# iot-enviroment-shield.net
KiCad netlist of a schematic drawn in EAGLE
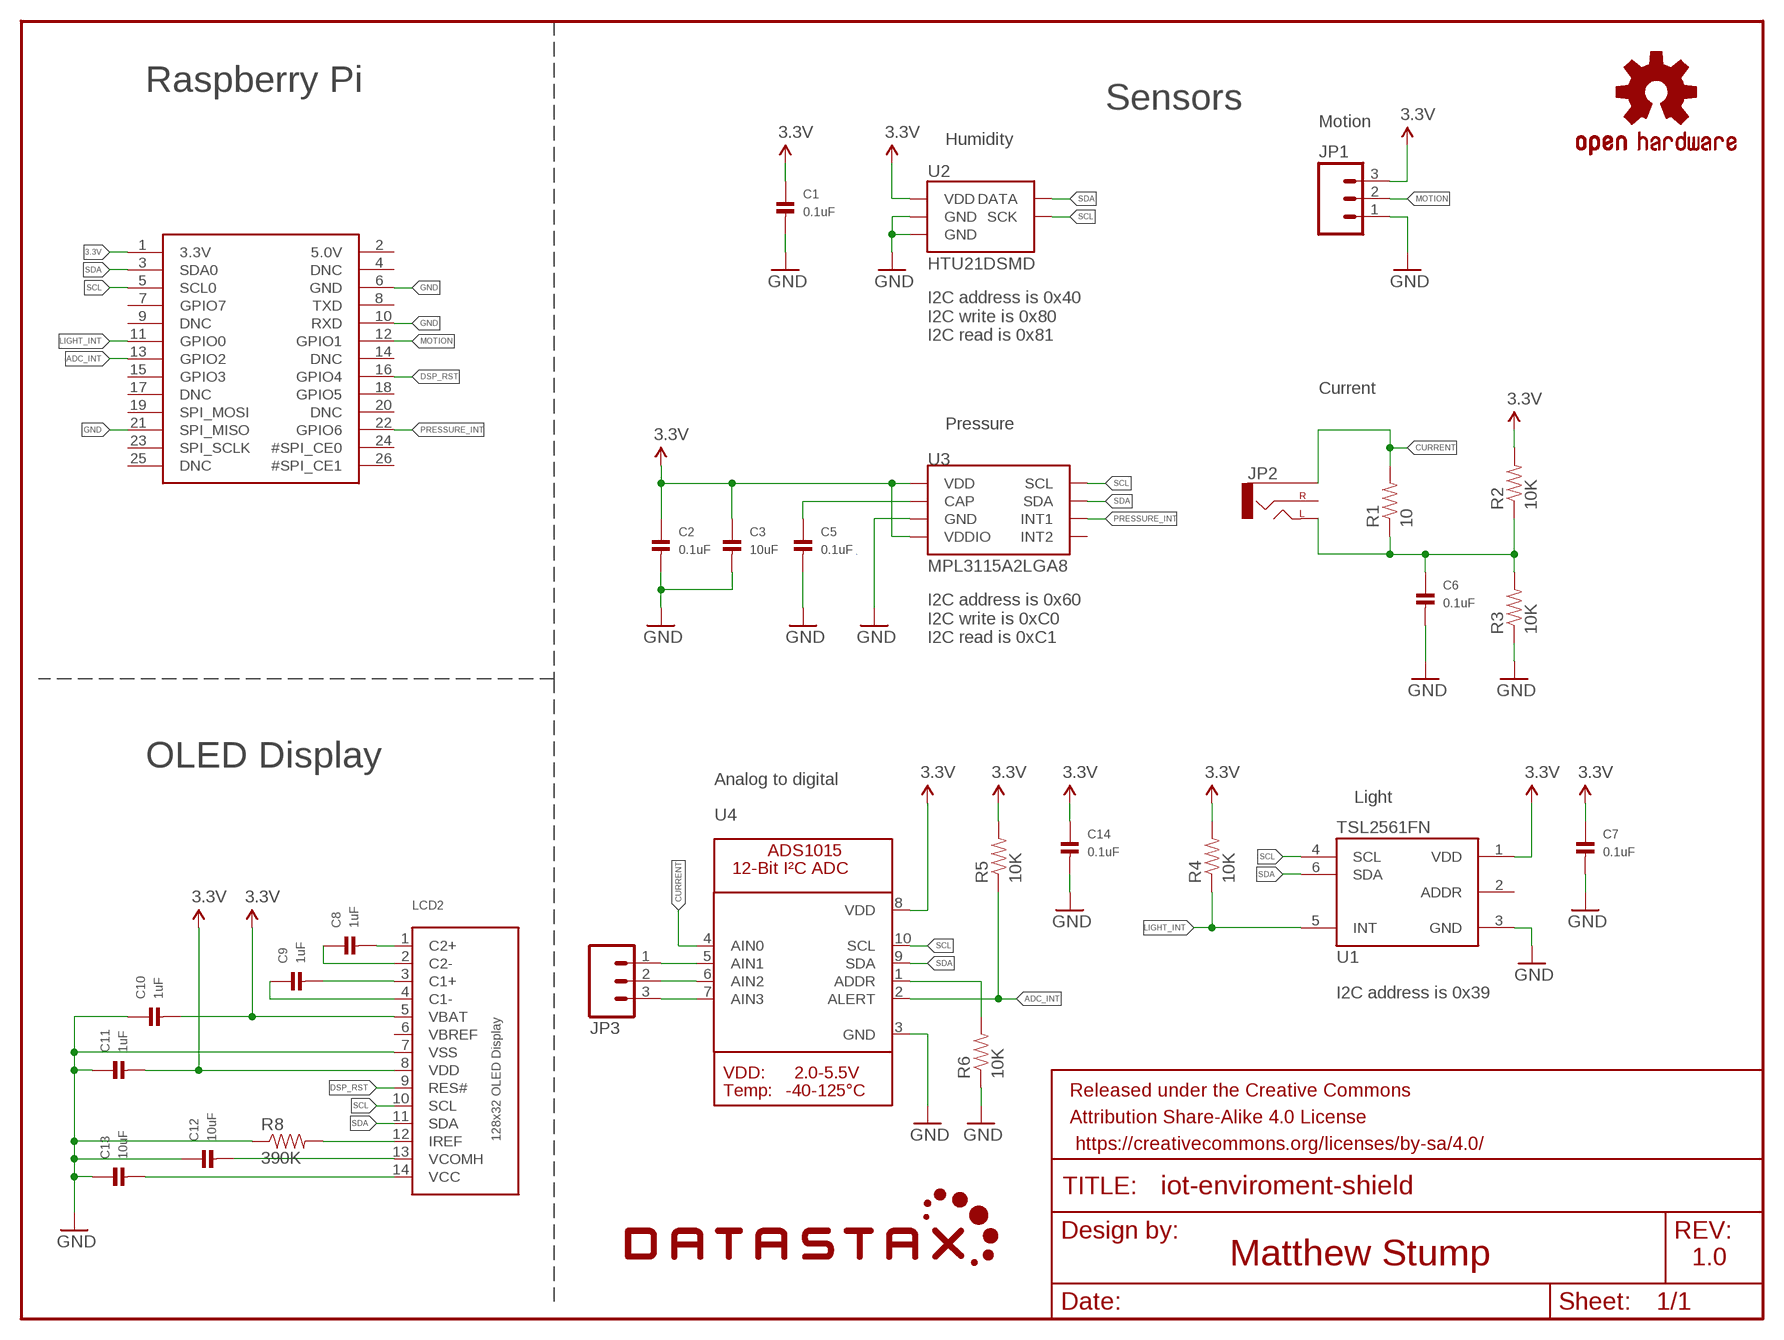
[diagram p0: schematic, sheet 1]

(export (version "E")
  (design (tool "Eeschema 10.0.6"))
  (components
    (comp (ref "C1")
      (value "0.1uF")
      (footprint "eagle-import:0603")
      (fields (field (name "MPN") "0603YC104JAT2A"))
      (libsource (lib "eagle-import") (part "CAP_CERAMIC0603"))
    )
    (comp (ref "C2")
      (value "0.1uF")
      (footprint "eagle-import:0603")
      (fields (field (name "MPN") "0603YC104JAT2A"))
      (libsource (lib "eagle-import") (part "CAP_CERAMIC0603"))
    )
    (comp (ref "C3")
      (value "10uF")
      (footprint "eagle-import:0603")
      (fields (field (name "MPN") "06035A100FAT2A"))
      (libsource (lib "eagle-import") (part "CAP_CERAMIC0603"))
    )
    (comp (ref "C5")
      (value "0.1uF")
      (footprint "eagle-import:0603")
      (fields (field (name "MPN") "0603YC104JAT2A"))
      (libsource (lib "eagle-import") (part "CAP_CERAMIC0603"))
    )
    (comp (ref "C6")
      (value "0.1uF")
      (footprint "eagle-import:0603")
      (fields (field (name "MPN") "0603YC104JAT2A"))
      (libsource (lib "eagle-import") (part "CAP_CERAMIC0603"))
    )
    (comp (ref "C7")
      (value "0.1uF")
      (footprint "eagle-import:0603")
      (fields (field (name "MPN") "0603YC104JAT2A"))
      (libsource (lib "eagle-import") (part "CAP_CERAMIC0603"))
    )
    (comp (ref "C8")
      (value "1uF")
      (footprint "eagle-import:0603")
      (fields (field (name "MF") "AVX CORPORATION") (field (name "MPN") "06036D105KAT2A"))
      (libsource (lib "eagle-import") (part "CAP_CERAMIC0603"))
    )
    (comp (ref "C9")
      (value "1uF")
      (footprint "eagle-import:0603")
      (fields (field (name "MF") "AVX CORPORATION") (field (name "MPN") "06036D105KAT2A"))
      (libsource (lib "eagle-import") (part "CAP_CERAMIC0603"))
    )
    (comp (ref "C10")
      (value "1uF")
      (footprint "eagle-import:0603")
      (fields (field (name "MF") "AVX CORPORATION") (field (name "MPN") "06036D105KAT2A"))
      (libsource (lib "eagle-import") (part "CAP_CERAMIC0603"))
    )
    (comp (ref "C11")
      (value "1uF")
      (footprint "eagle-import:0603")
      (fields (field (name "MF") "AVX CORPORATION") (field (name "MPN") "06036D105KAT2A"))
      (libsource (lib "eagle-import") (part "CAP_CERAMIC0603"))
    )
    (comp (ref "C12")
      (value "10uF")
      (footprint "eagle-import:0603")
      (fields (field (name "MPN") "06035A100FAT2A"))
      (libsource (lib "eagle-import") (part "CAP_CERAMIC0603"))
    )
    (comp (ref "C13")
      (value "10uF")
      (footprint "eagle-import:0603")
      (fields (field (name "MPN") "06035A100FAT2A"))
      (libsource (lib "eagle-import") (part "CAP_CERAMIC0603"))
    )
    (comp (ref "C14")
      (value "0.1uF")
      (footprint "eagle-import:0603")
      (fields (field (name "MPN") "0603YC104JAT2A"))
      (libsource (lib "eagle-import") (part "CAP_CERAMIC0603"))
    )
    (comp (ref "FRAME1")
      (value "FRAME-LETTER")
      (footprint "eagle-import:CREATIVE_COMMONS")
      (fields (field (name "OC_NEWARK") "unknown"))
      (libsource (lib "eagle-import") (part "FRAME-LETTER"))
    )
    (comp (ref "JP1")
      (value "M03SCREW")
      (footprint "eagle-import:SCREWTERMINAL-3.5MM-3")
      (fields (field (name "MF") "WEIDMULLER, INC.") (field (name "MPN") "1699680000"))
      (libsource (lib "eagle-import") (part "M03SCREW"))
    )
    (comp (ref "JP2")
      (value "AUDIO-JACKPTH")
      (footprint "eagle-import:AUDIO-JACK")
      (libsource (lib "eagle-import") (part "AUDIO-JACKPTH"))
    )
    (comp (ref "JP3")
      (value "M03SCREW")
      (footprint "eagle-import:SCREWTERMINAL-3.5MM-3")
      (fields (field (name "MF") "WEIDMULLER, INC.") (field (name "MPN") "1699680000"))
      (libsource (lib "eagle-import") (part "M03SCREW"))
    )
    (comp (ref "LCD2")
      (value "DISP_OLED_UG-2832HSWEG02")
      (footprint "eagle-import:UG-2832HSWEG02_WRAPUNDER")
      (libsource (lib "eagle-import") (part "DISP_OLED_UG-2832HSWEG02"))
    )
    (comp (ref "LOGO1")
      (value "OSHW-LOGOL")
      (footprint "eagle-import:OSHW-LOGO-L")
      (libsource (lib "eagle-import") (part "OSHW-LOGOL"))
    )
    (comp (ref "R1")
      (value "10")
      (footprint "eagle-import:0603-RES")
      (fields (field (name "MPN") "ERJ-3EKF10R0V"))
      (libsource (lib "eagle-import") (part "RESISTOR0603-RES"))
    )
    (comp (ref "R2")
      (value "10K")
      (footprint "eagle-import:0603-RES")
      (fields (field (name "MPN") "ERJ-P03F1002V"))
      (libsource (lib "eagle-import") (part "RESISTOR0603-RES"))
    )
    (comp (ref "R3")
      (value "10K")
      (footprint "eagle-import:0603-RES")
      (fields (field (name "MPN") "ERJ-P03F1002V"))
      (libsource (lib "eagle-import") (part "RESISTOR0603-RES"))
    )
    (comp (ref "R4")
      (value "10K")
      (footprint "eagle-import:0603-RES")
      (fields (field (name "MPN") "ERJ-P03F1002V"))
      (libsource (lib "eagle-import") (part "RESISTOR0603-RES"))
    )
    (comp (ref "R5")
      (value "10K")
      (footprint "eagle-import:0603-RES")
      (fields (field (name "MPN") "ERJ-P03F1002V"))
      (libsource (lib "eagle-import") (part "RESISTOR0603-RES"))
    )
    (comp (ref "R6")
      (value "10K")
      (footprint "eagle-import:0603-RES")
      (fields (field (name "MPN") "ERJ-P03F1002V"))
      (libsource (lib "eagle-import") (part "RESISTOR0603-RES"))
    )
    (comp (ref "R8")
      (value "390K")
      (footprint "eagle-import:0603-RES")
      (fields (field (name "MPN") "ERJ-P03F3903V"))
      (libsource (lib "eagle-import") (part "RESISTOR0603-RES"))
    )
    (comp (ref "U$1")
      (value "DATASTAX_LOGO")
      (footprint "eagle-import:DATASTAX_LOGO")
      (libsource (lib "eagle-import") (part "DATASTAX_LOGO"))
    )
    (comp (ref "U$2")
      (value "RASPBERRYPI_BB")
      (footprint "eagle-import:RASBERRYPI_SHIELD")
      (libsource (lib "eagle-import") (part "RASPBERRYPI_BB"))
    )
    (comp (ref "U1")
      (value "TSL2561FN")
      (footprint "eagle-import:FN-6")
      (fields (field (name "MPN") "TSL2561T"))
      (libsource (lib "eagle-import") (part "TSL2561FN"))
    )
    (comp (ref "U2")
      (value "HTU21DSMD")
      (footprint "eagle-import:HTU21D")
      (fields (field (name "MPN") "HTU21D"))
      (libsource (lib "eagle-import") (part "HTU21DSMD"))
    )
    (comp (ref "U3")
      (value "MPL3115A2LGA8")
      (footprint "eagle-import:LGA8")
      (fields (field (name "MPN") "MPL3115A2"))
      (libsource (lib "eagle-import") (part "MPL3115A2LGA8"))
    )
    (comp (ref "U4")
      (value "ADC_ADS1015")
      (footprint "eagle-import:MSOP10")
      (fields (field (name "MPN") "ADS1015IDGST"))
      (libsource (lib "eagle-import") (part "ADC_ADS1015"))
    )
  )
  (nets
    (net (code "1") (name "/5.0V") (class "Default")
      (node (ref "U$2") (pin "2") (pinfunction "5.0V_2") (pintype "power_in"))
    )
    (net (code "2") (name "/VBREF") (class "Default")
      (node (ref "LCD2") (pin "6") (pinfunction "VBREF_6") (pintype "power_in"))
    )
    (net (code "3") (name "3.3V") (class "Default")
      (node (ref "C1") (pin "1") (pinfunction "P$1_1") (pintype "passive"))
      (node (ref "C10") (pin "2") (pinfunction "P$2_2") (pintype "passive"))
      (node (ref "C11") (pin "2") (pinfunction "P$2_2") (pintype "passive"))
      (node (ref "C14") (pin "1") (pinfunction "P$1_1") (pintype "passive"))
      (node (ref "C2") (pin "1") (pinfunction "P$1_1") (pintype "passive"))
      (node (ref "C3") (pin "1") (pinfunction "P$1_1") (pintype "passive"))
      (node (ref "C7") (pin "1") (pinfunction "P$1_1") (pintype "passive"))
      (node (ref "JP1") (pin "3") (pinfunction "3_3") (pintype "passive"))
      (node (ref "LCD2") (pin "5") (pinfunction "VBAT_5") (pintype "power_in"))
      (node (ref "LCD2") (pin "8") (pinfunction "VDD_8") (pintype "power_in"))
      (node (ref "R2") (pin "2") (pinfunction "2_2") (pintype "passive"))
      (node (ref "R4") (pin "2") (pinfunction "2_2") (pintype "passive"))
      (node (ref "R5") (pin "2") (pinfunction "2_2") (pintype "passive"))
      (node (ref "U$2") (pin "1") (pinfunction "3.3V_1") (pintype "power_in"))
      (node (ref "U1") (pin "1") (pinfunction "VDD_1") (pintype "power_in"))
      (node (ref "U2") (pin "VDD") (pinfunction "VDD_VDD") (pintype "power_in"))
      (node (ref "U3") (pin "1") (pinfunction "VDD_1") (pintype "power_in"))
      (node (ref "U3") (pin "4") (pinfunction "VDDIO_4") (pintype "power_in"))
      (node (ref "U4") (pin "8") (pinfunction "VDD_8") (pintype "bidirectional"))
    )
    (net (code "4") (name "ADC_INT") (class "Default")
      (node (ref "R5") (pin "1") (pinfunction "1_1") (pintype "passive"))
      (node (ref "U$2") (pin "13") (pinfunction "GPIO2_13") (pintype "bidirectional"))
      (node (ref "U4") (pin "2") (pinfunction "ALERT_2") (pintype "bidirectional"))
    )
    (net (code "5") (name "CURRENT") (class "Default")
      (node (ref "JP2") (pin "SLEEVE") (pinfunction "SLEEVE_SLEEVE") (pintype "bidirectional"))
      (node (ref "R1") (pin "2") (pinfunction "2_2") (pintype "passive"))
      (node (ref "U4") (pin "4") (pinfunction "AIN0_4") (pintype "bidirectional"))
    )
    (net (code "6") (name "DSP_RST") (class "Default")
      (node (ref "LCD2") (pin "9") (pinfunction "RES#_9") (pintype "bidirectional"))
      (node (ref "U$2") (pin "16") (pinfunction "GPIO4_16") (pintype "bidirectional"))
    )
    (net (code "7") (name "GND") (class "Default")
      (node (ref "C1") (pin "2") (pinfunction "P$2_2") (pintype "passive"))
      (node (ref "C10") (pin "1") (pinfunction "P$1_1") (pintype "passive"))
      (node (ref "C11") (pin "1") (pinfunction "P$1_1") (pintype "passive"))
      (node (ref "C12") (pin "1") (pinfunction "P$1_1") (pintype "passive"))
      (node (ref "C13") (pin "1") (pinfunction "P$1_1") (pintype "passive"))
      (node (ref "C14") (pin "2") (pinfunction "P$2_2") (pintype "passive"))
      (node (ref "C2") (pin "2") (pinfunction "P$2_2") (pintype "passive"))
      (node (ref "C3") (pin "2") (pinfunction "P$2_2") (pintype "passive"))
      (node (ref "C5") (pin "2") (pinfunction "P$2_2") (pintype "passive"))
      (node (ref "C6") (pin "2") (pinfunction "P$2_2") (pintype "passive"))
      (node (ref "C7") (pin "2") (pinfunction "P$2_2") (pintype "passive"))
      (node (ref "JP1") (pin "1") (pinfunction "1_1") (pintype "passive"))
      (node (ref "LCD2") (pin "7") (pinfunction "VSS_7") (pintype "power_in"))
      (node (ref "R3") (pin "1") (pinfunction "1_1") (pintype "passive"))
      (node (ref "R6") (pin "1") (pinfunction "1_1") (pintype "passive"))
      (node (ref "R8") (pin "1") (pinfunction "1_1") (pintype "passive"))
      (node (ref "U$2") (pin "10") (pinfunction "RXD_10") (pintype "input"))
      (node (ref "U$2") (pin "21") (pinfunction "SPI_MISO_21") (pintype "input"))
      (node (ref "U$2") (pin "6") (pinfunction "GND_6") (pintype "power_in"))
      (node (ref "U1") (pin "3") (pinfunction "GND_3") (pintype "power_in"))
      (node (ref "U2") (pin "7") (pinfunction "GND_7") (pintype "power_in"))
      (node (ref "U2") (pin "GND") (pinfunction "GND_GND") (pintype "power_in"))
      (node (ref "U3") (pin "3") (pinfunction "GND_3") (pintype "power_in"))
      (node (ref "U4") (pin "3") (pinfunction "GND_3") (pintype "bidirectional"))
    )
    (net (code "8") (name "LIGHT_INT") (class "Default")
      (node (ref "R4") (pin "1") (pinfunction "1_1") (pintype "passive"))
      (node (ref "U$2") (pin "11") (pinfunction "GPIO0_11") (pintype "bidirectional"))
      (node (ref "U1") (pin "5") (pinfunction "INT_5") (pintype "output"))
    )
    (net (code "9") (name "MOTION") (class "Default")
      (node (ref "JP1") (pin "2") (pinfunction "2_2") (pintype "passive"))
      (node (ref "U$2") (pin "12") (pinfunction "GPIO1_12") (pintype "bidirectional"))
    )
    (net (code "10") (name "Net-(C5-P$1)") (class "Default")
      (node (ref "C5") (pin "1") (pinfunction "P$1_1") (pintype "passive"))
      (node (ref "U3") (pin "2") (pinfunction "CAP_2") (pintype "power_in"))
    )
    (net (code "11") (name "Net-(C6-P$1)") (class "Default")
      (node (ref "C6") (pin "1") (pinfunction "P$1_1") (pintype "passive"))
      (node (ref "JP2") (pin "TIP") (pinfunction "LEFT_TIP") (pintype "bidirectional"))
      (node (ref "R1") (pin "1") (pinfunction "1_1") (pintype "passive"))
      (node (ref "R2") (pin "1") (pinfunction "1_1") (pintype "passive"))
      (node (ref "R3") (pin "2") (pinfunction "2_2") (pintype "passive"))
    )
    (net (code "12") (name "Net-(C8-P$1)") (class "Default")
      (node (ref "C8") (pin "1") (pinfunction "P$1_1") (pintype "passive"))
      (node (ref "LCD2") (pin "2") (pinfunction "C2-_2") (pintype "bidirectional"))
    )
    (net (code "13") (name "Net-(C8-P$2)") (class "Default")
      (node (ref "C8") (pin "2") (pinfunction "P$2_2") (pintype "passive"))
      (node (ref "LCD2") (pin "1") (pinfunction "C2+_1") (pintype "bidirectional"))
    )
    (net (code "14") (name "Net-(C9-P$1)") (class "Default")
      (node (ref "C9") (pin "1") (pinfunction "P$1_1") (pintype "passive"))
      (node (ref "LCD2") (pin "4") (pinfunction "C1-_4") (pintype "bidirectional"))
    )
    (net (code "15") (name "Net-(C9-P$2)") (class "Default")
      (node (ref "C9") (pin "2") (pinfunction "P$2_2") (pintype "passive"))
      (node (ref "LCD2") (pin "3") (pinfunction "C1+_3") (pintype "bidirectional"))
    )
    (net (code "16") (name "Net-(C12-P$2)") (class "Default")
      (node (ref "C12") (pin "2") (pinfunction "P$2_2") (pintype "passive"))
      (node (ref "LCD2") (pin "13") (pinfunction "VCOMH_13") (pintype "power_in"))
    )
    (net (code "17") (name "Net-(C13-P$2)") (class "Default")
      (node (ref "C13") (pin "2") (pinfunction "P$2_2") (pintype "passive"))
      (node (ref "LCD2") (pin "14") (pinfunction "VCC_14") (pintype "power_in"))
    )
    (net (code "18") (name "Net-(LCD2-IREF)") (class "Default")
      (node (ref "LCD2") (pin "12") (pinfunction "IREF_12") (pintype "bidirectional"))
      (node (ref "R8") (pin "2") (pinfunction "2_2") (pintype "passive"))
    )
    (net (code "19") (name "Net-(U4-ADDR)") (class "Default")
      (node (ref "R6") (pin "2") (pinfunction "2_2") (pintype "passive"))
      (node (ref "U4") (pin "1") (pinfunction "ADDR_1") (pintype "bidirectional"))
    )
    (net (code "20") (name "Net-(U4-AIN1)") (class "Default")
      (node (ref "JP3") (pin "1") (pinfunction "1_1") (pintype "passive"))
      (node (ref "U4") (pin "5") (pinfunction "AIN1_5") (pintype "bidirectional"))
    )
    (net (code "21") (name "Net-(U4-AIN2)") (class "Default")
      (node (ref "JP3") (pin "2") (pinfunction "2_2") (pintype "passive"))
      (node (ref "U4") (pin "6") (pinfunction "AIN2_6") (pintype "bidirectional"))
    )
    (net (code "22") (name "Net-(U4-AIN3)") (class "Default")
      (node (ref "JP3") (pin "3") (pinfunction "3_3") (pintype "passive"))
      (node (ref "U4") (pin "7") (pinfunction "AIN3_7") (pintype "bidirectional"))
    )
    (net (code "23") (name "PRESSURE_INT") (class "Default")
      (node (ref "U$2") (pin "22") (pinfunction "GPIO6_22") (pintype "bidirectional"))
      (node (ref "U3") (pin "6") (pinfunction "INT1_6") (pintype "output"))
    )
    (net (code "24") (name "SCL") (class "Default")
      (node (ref "LCD2") (pin "10") (pinfunction "SCL_10") (pintype "bidirectional"))
      (node (ref "U$2") (pin "5") (pinfunction "SCL0_5") (pintype "output"))
      (node (ref "U1") (pin "4") (pinfunction "SCL_4") (pintype "input"))
      (node (ref "U2") (pin "SCK") (pinfunction "SCK_SCK") (pintype "input"))
      (node (ref "U3") (pin "8") (pinfunction "SCL_8") (pintype "bidirectional"))
      (node (ref "U4") (pin "10") (pinfunction "SCL_10") (pintype "bidirectional"))
    )
    (net (code "25") (name "SDA") (class "Default")
      (node (ref "LCD2") (pin "11") (pinfunction "SDA_11") (pintype "bidirectional"))
      (node (ref "U$2") (pin "3") (pinfunction "SDA0_3") (pintype "bidirectional"))
      (node (ref "U1") (pin "6") (pinfunction "SDA_6") (pintype "bidirectional"))
      (node (ref "U2") (pin "DATA") (pinfunction "DATA_DATA") (pintype "bidirectional"))
      (node (ref "U3") (pin "7") (pinfunction "SDA_7") (pintype "bidirectional"))
      (node (ref "U4") (pin "9") (pinfunction "SDA_9") (pintype "bidirectional"))
    )
    (net (code "26") (name "unconnected-(JP2-RIGHT-PadRING)") (class "Default")
      (node (ref "JP2") (pin "RING") (pinfunction "RIGHT_RING") (pintype "bidirectional"))
    )
    (net (code "27") (name "unconnected-(U$2-#SPI_CE0-Pad24)") (class "Default")
      (node (ref "U$2") (pin "24") (pinfunction "#SPI_CE0_24") (pintype "output"))
    )
    (net (code "28") (name "unconnected-(U$2-#SPI_CE1-Pad26)") (class "Default")
      (node (ref "U$2") (pin "26") (pinfunction "#SPI_CE1_26") (pintype "output"))
    )
    (net (code "29") (name "unconnected-(U$2-DNC-Pad4)") (class "Default")
      (node (ref "U$2") (pin "4") (pinfunction "DNC_4") (pintype "no_connect"))
    )
    (net (code "30") (name "unconnected-(U$2-DNC-Pad9)") (class "Default")
      (node (ref "U$2") (pin "9") (pinfunction "DNC_9") (pintype "no_connect"))
    )
    (net (code "31") (name "unconnected-(U$2-DNC-Pad14)") (class "Default")
      (node (ref "U$2") (pin "14") (pinfunction "DNC_14") (pintype "no_connect"))
    )
    (net (code "32") (name "unconnected-(U$2-DNC-Pad17)") (class "Default")
      (node (ref "U$2") (pin "17") (pinfunction "DNC_17") (pintype "no_connect"))
    )
    (net (code "33") (name "unconnected-(U$2-DNC-Pad20)") (class "Default")
      (node (ref "U$2") (pin "20") (pinfunction "DNC_20") (pintype "no_connect"))
    )
    (net (code "34") (name "unconnected-(U$2-DNC-Pad25)") (class "Default")
      (node (ref "U$2") (pin "25") (pinfunction "DNC_25") (pintype "no_connect"))
    )
    (net (code "35") (name "unconnected-(U$2-GPIO3-Pad15)") (class "Default")
      (node (ref "U$2") (pin "15") (pinfunction "GPIO3_15") (pintype "bidirectional"))
    )
    (net (code "36") (name "unconnected-(U$2-GPIO5-Pad18)") (class "Default")
      (node (ref "U$2") (pin "18") (pinfunction "GPIO5_18") (pintype "bidirectional"))
    )
    (net (code "37") (name "unconnected-(U$2-GPIO7-Pad7)") (class "Default")
      (node (ref "U$2") (pin "7") (pinfunction "GPIO7_7") (pintype "bidirectional"))
    )
    (net (code "38") (name "unconnected-(U$2-SPI_MOSI-Pad19)") (class "Default")
      (node (ref "U$2") (pin "19") (pinfunction "SPI_MOSI_19") (pintype "output"))
    )
    (net (code "39") (name "unconnected-(U$2-SPI_SCLK-Pad23)") (class "Default")
      (node (ref "U$2") (pin "23") (pinfunction "SPI_SCLK_23") (pintype "output"))
    )
    (net (code "40") (name "unconnected-(U$2-TXD-Pad8)") (class "Default")
      (node (ref "U$2") (pin "8") (pinfunction "TXD_8") (pintype "output"))
    )
    (net (code "41") (name "unconnected-(U1-ADDR-Pad2)") (class "Default")
      (node (ref "U1") (pin "2") (pinfunction "ADDR_2") (pintype "input"))
    )
    (net (code "42") (name "unconnected-(U3-INT2-Pad5)") (class "Default")
      (node (ref "U3") (pin "5") (pinfunction "INT2_5") (pintype "output"))
    )
  )
)
